# TransistorHightKeyBoard.net
KiCad netlist of a schematic drawn in Altium Designer
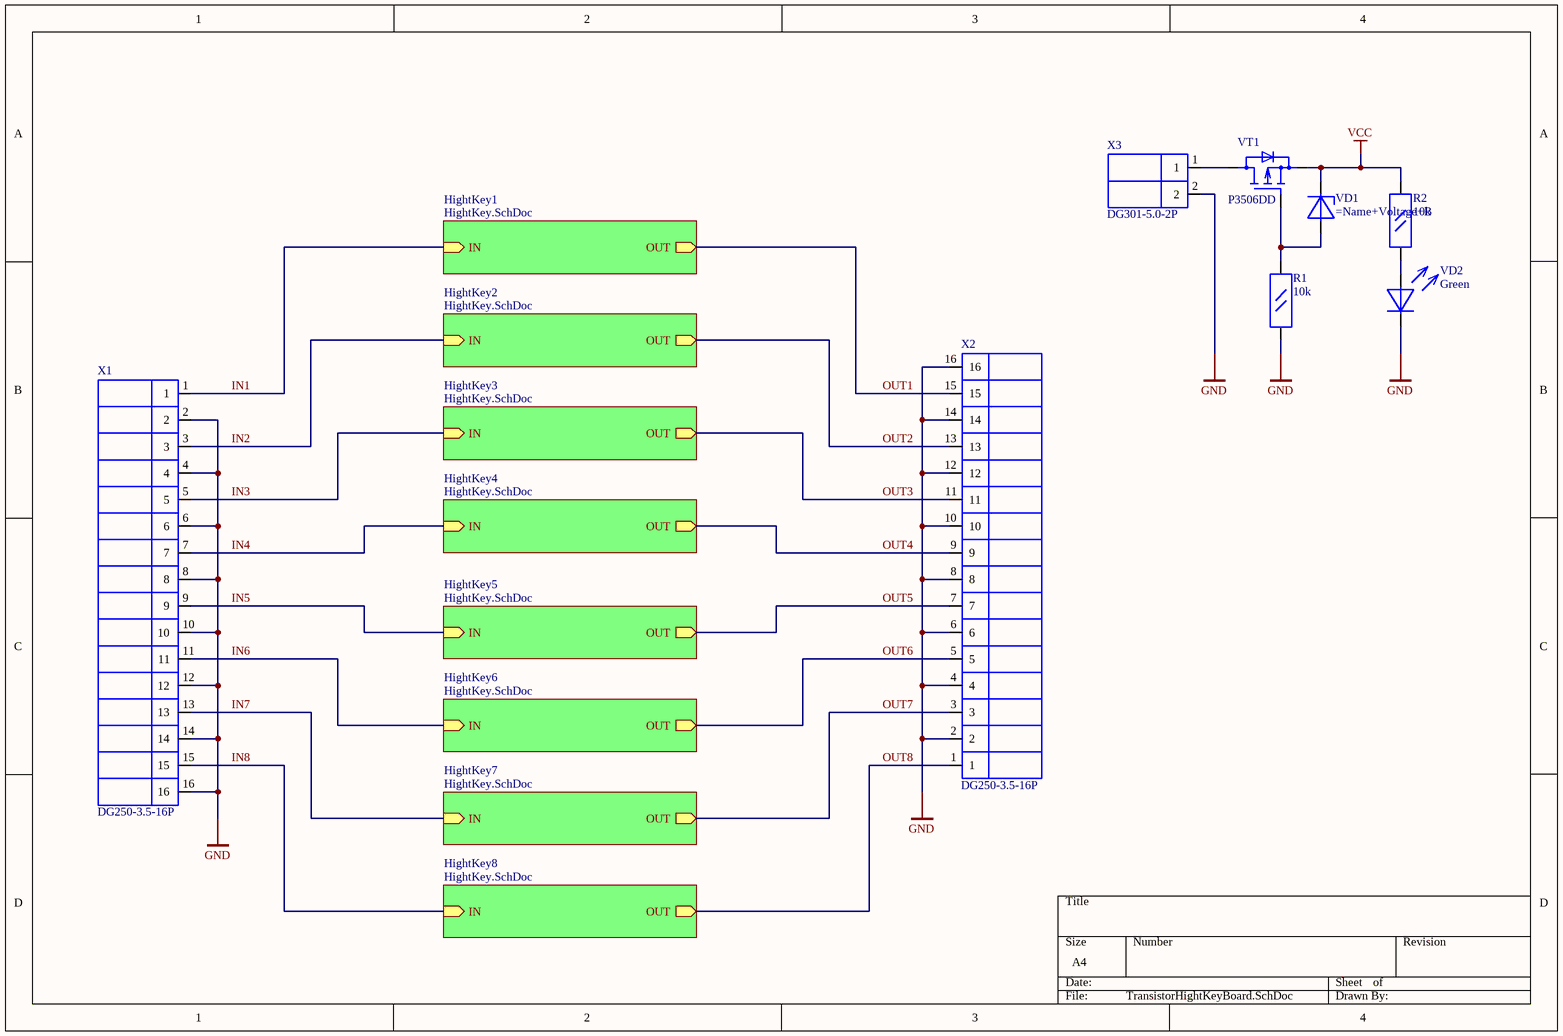
[diagram p0: TransistorHightKeyBoard.SchDoc]

(export (version "E")
  (design (tool "Eeschema 10.0.6"))
  (components
    (comp (ref "R1")
      (value "R0805")
      (footprint "RES0805")
      (description "Resistor")
      (fields (field (name "RESISTANCE (OHMS)") "10k"))
      (libsource (lib "zvemake_int_lib") (part "R0805"))
    )
    (comp (ref "R2")
      (value "R0805")
      (footprint "RES0805")
      (description "Resistor")
      (fields (field (name "RESISTANCE (OHMS)") "10k"))
      (libsource (lib "zvemake_int_lib") (part "R0805"))
    )
    (comp (ref "VD1")
      (value "PDZ12")
      (footprint "SOD323")
      (description "Diode")
      (fields (field (name "VOLTAGE") "12"))
      (libsource (lib "zvemake_int_lib") (part "PDZ-B"))
    )
    (comp (ref "VD2")
      (value "Led Green 3mm")
      (footprint "3mm led green")
      (description "3mm Green Led 2.54pitch")
      (fields (field (name "COLOR") "Green"))
      (libsource (lib "zvemake_int_lib") (part "Led Green 3mm"))
    )
    (comp (ref "VT1")
      (value "P3506DD")
      (footprint "DPAK")
      (description "P-channel MOSFET transistor")
      (fields (field (name "MANUFACTURER") "NIKO SEMICONDUCTOR CO"))
      (libsource (lib "zvemake_int_lib") (part "P3506DD"))
    )
    (comp (ref "X1")
      (value "DG250-3.5-16P")
      (footprint "DG250-3.5-16P")
      (description "5mm Pitch PCB Terminal Block Connector")
      (libsource (lib "zvemake_int_lib") (part "DG250-3.5-16P"))
    )
    (comp (ref "X2")
      (value "DG250-3.5-16P")
      (footprint "DG250-3.5-16P")
      (description "5mm Pitch PCB Terminal Block Connector")
      (libsource (lib "zvemake_int_lib") (part "DG250-3.5-16P"))
    )
    (comp (ref "X3")
      (value "DG301-5.0-2P")
      (footprint "DG301-5.0-2P")
      (description "5mm Pitch PCB Terminal Block Connector")
      (libsource (lib "zvemake_int_lib") (part "DG301-5.0-2P"))
    )
  )
  (nets
    (net (code "1") (name "/IN1") (class "Default")
      (node (ref "X1") (pin "1") (pinfunction "1_1") (pintype "passive"))
    )
    (net (code "2") (name "/IN2") (class "Default")
      (node (ref "X1") (pin "3") (pinfunction "3_3") (pintype "passive"))
    )
    (net (code "3") (name "/IN3") (class "Default")
      (node (ref "X1") (pin "5") (pinfunction "5_5") (pintype "passive"))
    )
    (net (code "4") (name "/IN4") (class "Default")
      (node (ref "X1") (pin "7") (pinfunction "7_7") (pintype "passive"))
    )
    (net (code "5") (name "/IN5") (class "Default")
      (node (ref "X1") (pin "9") (pinfunction "9_9") (pintype "passive"))
    )
    (net (code "6") (name "/IN6") (class "Default")
      (node (ref "X1") (pin "11") (pinfunction "11_11") (pintype "passive"))
    )
    (net (code "7") (name "/IN7") (class "Default")
      (node (ref "X1") (pin "13") (pinfunction "13_13") (pintype "passive"))
    )
    (net (code "8") (name "/IN8") (class "Default")
      (node (ref "X1") (pin "15") (pinfunction "15_15") (pintype "passive"))
    )
    (net (code "9") (name "/OUT1") (class "Default")
      (node (ref "X2") (pin "15") (pinfunction "15_15") (pintype "passive"))
    )
    (net (code "10") (name "/OUT2") (class "Default")
      (node (ref "X2") (pin "13") (pinfunction "13_13") (pintype "passive"))
    )
    (net (code "11") (name "/OUT3") (class "Default")
      (node (ref "X2") (pin "11") (pinfunction "11_11") (pintype "passive"))
    )
    (net (code "12") (name "/OUT4") (class "Default")
      (node (ref "X2") (pin "9") (pinfunction "9_9") (pintype "passive"))
    )
    (net (code "13") (name "/OUT5") (class "Default")
      (node (ref "X2") (pin "7") (pinfunction "7_7") (pintype "passive"))
    )
    (net (code "14") (name "/OUT6") (class "Default")
      (node (ref "X2") (pin "5") (pinfunction "5_5") (pintype "passive"))
    )
    (net (code "15") (name "/OUT7") (class "Default")
      (node (ref "X2") (pin "3") (pinfunction "3_3") (pintype "passive"))
    )
    (net (code "16") (name "/OUT8") (class "Default")
      (node (ref "X2") (pin "1") (pinfunction "1_1") (pintype "passive"))
    )
    (net (code "17") (name "GND") (class "Default")
      (node (ref "R1") (pin "1") (pinfunction "1_1") (pintype "passive"))
      (node (ref "VD2") (pin "1") (pinfunction "C_1") (pintype "passive"))
      (node (ref "X1") (pin "10") (pinfunction "10_10") (pintype "passive"))
      (node (ref "X1") (pin "12") (pinfunction "12_12") (pintype "passive"))
      (node (ref "X1") (pin "14") (pinfunction "14_14") (pintype "passive"))
      (node (ref "X1") (pin "16") (pinfunction "16_16") (pintype "passive"))
      (node (ref "X1") (pin "2") (pinfunction "2_2") (pintype "passive"))
      (node (ref "X1") (pin "4") (pinfunction "4_4") (pintype "passive"))
      (node (ref "X1") (pin "6") (pinfunction "6_6") (pintype "passive"))
      (node (ref "X1") (pin "8") (pinfunction "8_8") (pintype "passive"))
      (node (ref "X2") (pin "10") (pinfunction "10_10") (pintype "passive"))
      (node (ref "X2") (pin "12") (pinfunction "12_12") (pintype "passive"))
      (node (ref "X2") (pin "14") (pinfunction "14_14") (pintype "passive"))
      (node (ref "X2") (pin "16") (pinfunction "16_16") (pintype "passive"))
      (node (ref "X2") (pin "2") (pinfunction "2_2") (pintype "passive"))
      (node (ref "X2") (pin "4") (pinfunction "4_4") (pintype "passive"))
      (node (ref "X2") (pin "6") (pinfunction "6_6") (pintype "passive"))
      (node (ref "X2") (pin "8") (pinfunction "8_8") (pintype "passive"))
      (node (ref "X3") (pin "2") (pinfunction "2_2") (pintype "passive"))
    )
    (net (code "18") (name "Net-(VD1-A)") (class "Default")
      (node (ref "R1") (pin "2") (pinfunction "2_2") (pintype "passive"))
      (node (ref "VD1") (pin "2") (pinfunction "A_2") (pintype "passive"))
      (node (ref "VT1") (pin "1") (pinfunction "G_1") (pintype "passive"))
    )
    (net (code "19") (name "Net-(VD2-A)") (class "Default")
      (node (ref "R2") (pin "1") (pinfunction "1_1") (pintype "passive"))
      (node (ref "VD2") (pin "2") (pinfunction "A_2") (pintype "passive"))
    )
    (net (code "20") (name "Net-(VT1-D)") (class "Default")
      (node (ref "VT1") (pin "2") (pinfunction "D_2") (pintype "passive"))
      (node (ref "X3") (pin "1") (pinfunction "1_1") (pintype "passive"))
    )
    (net (code "21") (name "VCC") (class "Default")
      (node (ref "R2") (pin "2") (pinfunction "2_2") (pintype "passive"))
      (node (ref "VD1") (pin "1") (pinfunction "C_1") (pintype "passive"))
      (node (ref "VT1") (pin "3") (pinfunction "S_3") (pintype "passive"))
    )
  )
)
